# PreciseGNSS.net
KiCad netlist of a schematic drawn in Altium Designer
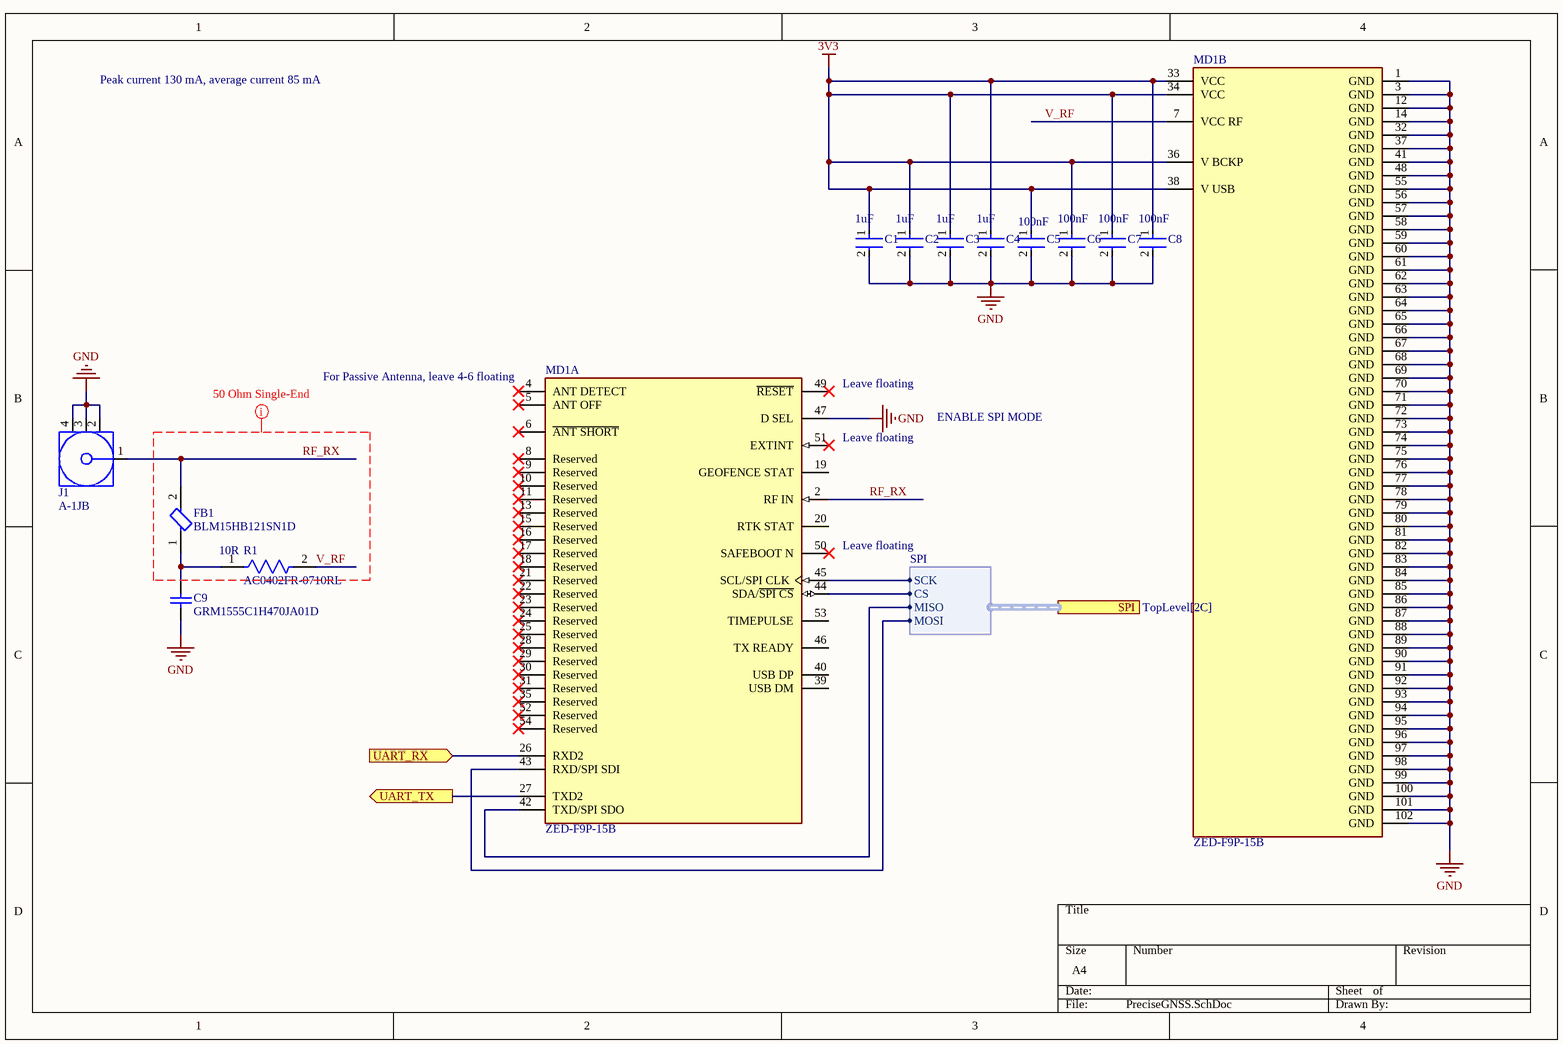
[diagram p0: PreciseGNSS.SchDoc]

(export (version "E")
  (design (tool "Eeschema 10.0.6"))
  (components
    (comp (ref "C1")
      (value "CL05A105KP5NNNC")
      (footprint "FP-CL511-IPC_C")
      (description "Cap Ceramic 1uF 10V X5R ±10% SMD 0402 +85°C Paper T/R")
      (fields (field (name "CAPACITANCE") "1uF") (field (name "TOLERANCE") "10%"))
      (libsource (lib "Altium Content Vault") (part "b4654b650e69147ec39a6b967a45e02"))
    )
    (comp (ref "C2")
      (value "CL05A105KP5NNNC")
      (footprint "FP-CL511-IPC_C")
      (description "Cap Ceramic 1uF 10V X5R ±10% SMD 0402 +85°C Paper T/R")
      (fields (field (name "CAPACITANCE") "1uF") (field (name "TOLERANCE") "10%"))
      (libsource (lib "Altium Content Vault") (part "b4654b650e69147ec39a6b967a45e02"))
    )
    (comp (ref "C3")
      (value "CL05A105KP5NNNC")
      (footprint "FP-CL511-IPC_C")
      (description "Cap Ceramic 1uF 10V X5R ±10% SMD 0402 +85°C Paper T/R")
      (fields (field (name "CAPACITANCE") "1uF") (field (name "TOLERANCE") "10%"))
      (libsource (lib "Altium Content Vault") (part "b4654b650e69147ec39a6b967a45e02"))
    )
    (comp (ref "C4")
      (value "CL05A105KP5NNNC")
      (footprint "FP-CL511-IPC_C")
      (description "Cap Ceramic 1uF 10V X5R ±10% SMD 0402 +85°C Paper T/R")
      (fields (field (name "CAPACITANCE") "1uF") (field (name "TOLERANCE") "10%"))
      (libsource (lib "Altium Content Vault") (part "b4654b650e69147ec39a6b967a45e02"))
    )
    (comp (ref "C5")
      (value "GRM155R71E104KE14J")
      (footprint "FP-GRM155-0_05-IPC_C")
      (description "Chip Multilayer Ceramic Capacitors for General Purpose, 0402, 0.10uF, X7R, 15%, 10%, 25V")
      (fields (field (name "CAPACITANCE") "100nF") (field (name "TOLERANCE") "10%"))
      (libsource (lib "Altium Content Vault") (part "02cd4be3c70576c341d710602a673aa"))
    )
    (comp (ref "C6")
      (value "GRM155R71E104KE14J")
      (footprint "FP-GRM155-0_05-IPC_C")
      (description "Chip Multilayer Ceramic Capacitors for General Purpose, 0402, 0.10uF, X7R, 15%, 10%, 25V")
      (fields (field (name "CAPACITANCE") "100nF") (field (name "TOLERANCE") "10%"))
      (libsource (lib "Altium Content Vault") (part "02cd4be3c70576c341d710602a673aa"))
    )
    (comp (ref "C7")
      (value "GRM155R71E104KE14J")
      (footprint "FP-GRM155-0_05-IPC_C")
      (description "Chip Multilayer Ceramic Capacitors for General Purpose, 0402, 0.10uF, X7R, 15%, 10%, 25V")
      (fields (field (name "CAPACITANCE") "100nF") (field (name "TOLERANCE") "10%"))
      (libsource (lib "Altium Content Vault") (part "02cd4be3c70576c341d710602a673aa"))
    )
    (comp (ref "C8")
      (value "GRM155R71E104KE14J")
      (footprint "FP-GRM155-0_05-IPC_C")
      (description "Chip Multilayer Ceramic Capacitors for General Purpose, 0402, 0.10uF, X7R, 15%, 10%, 25V")
      (fields (field (name "CAPACITANCE") "100nF") (field (name "TOLERANCE") "10%"))
      (libsource (lib "Altium Content Vault") (part "02cd4be3c70576c341d710602a673aa"))
    )
    (comp (ref "C9")
      (value "GRM1555C1H470JA01D")
      (footprint "CAPC1005X55X25LL05T10")
      (fields (field (name "MANUFACTURER") "Murata"))
      (libsource (lib "Altium Content Vault") (part "CAP"))
    )
    (comp (ref "FB1")
      (value "BLM15HB121SN1D")
      (footprint "FP-BLM15-0_05-IPC_B")
      (description "Chip Ferrite Bead, 0402, 120Ω @ 100MHz, 0.7Ω, 25%, 300mA")
      (fields (field (name "TOLERANCE") "25%"))
      (libsource (lib "Altium Content Vault") (part "5f30dd21d616792df468990f7003faa"))
    )
    (comp (ref "J1")
      (value "A-1JB")
      (footprint "AMPH-A-1JB_V")
      (description "AMC PCB Jack, 0 to 60 GHz, 60 V, -40 to 90 degC, 4-Pin SMD, RoHS, Tape and Reel")
      (fields (field (name "TOLERANCE") "10%"))
      (libsource (lib "Altium Content Vault") (part "CN-S-3F-RF4"))
    )
    (comp (ref "MD1")
      (value "ZED-F9P-15B")
      (footprint "FP-ZED-F9P-15B-MFG")
      (description "ZED-F9P-15B GNSS / GPS Modules u-blox F9 dual band L1/L5 GNSS module high precision Professi")
      (libsource (lib "Altium Content Vault") (part "967c5f9512e66fc8cb632c41bffe964"))
    )
    (comp (ref "R1")
      (value "AC0402FR-0710RL")
      (footprint "FP-AC0402-IPC_B")
      (description "RES 10Ω ±1% 0.063W 0402")
      (fields (field (name "TOLERANCE") "1%") (field (name "RESISTANCE") "10R"))
      (libsource (lib "Altium Content Vault") (part "1029c3af85768c4190bb7ad29bc67b5"))
    )
  )
  (nets
    (net (code "2") (name "/CS") (class "Default")
      (node (ref "MD1") (pin "44") (pinfunction "SDA/~{SPI_CS}_44") (pintype "bidirectional"))
    )
    (net (code "3") (name "/MISO") (class "Default")
      (node (ref "MD1") (pin "42") (pinfunction "TXD/SPI_SDO_42") (pintype "passive"))
    )
    (net (code "4") (name "/MOSI") (class "Default")
      (node (ref "MD1") (pin "43") (pinfunction "RXD/SPI_SDI_43") (pintype "passive"))
    )
    (net (code "5") (name "/RF_RX") (class "Default")
      (node (ref "FB1") (pin "2") (pinfunction "2_2") (pintype "passive"))
      (node (ref "J1") (pin "1") (pinfunction "1_1") (pintype "passive"))
      (node (ref "MD1") (pin "2") (pinfunction "RF_IN_2") (pintype "input"))
    )
    (net (code "6") (name "/SCK") (class "Default")
      (node (ref "MD1") (pin "45") (pinfunction "SCL/SPI_CLK_45") (pintype "input"))
    )
    (net (code "7") (name "/UART_RX") (class "Default")
      (node (ref "MD1") (pin "26") (pinfunction "RXD2_26") (pintype "passive"))
    )
    (net (code "8") (name "/UART_TX") (class "Default")
      (node (ref "MD1") (pin "27") (pinfunction "TXD2_27") (pintype "passive"))
    )
    (net (code "9") (name "/V_RF") (class "Default")
      (node (ref "MD1") (pin "7") (pinfunction "VCC_RF_7") (pintype "passive"))
      (node (ref "R1") (pin "2") (pinfunction "2_2") (pintype "passive"))
    )
    (net (code "11") (name "3V3") (class "Default")
      (node (ref "C1") (pin "1") (pinfunction "1_1") (pintype "passive"))
      (node (ref "C2") (pin "1") (pinfunction "1_1") (pintype "passive"))
      (node (ref "C3") (pin "1") (pinfunction "1_1") (pintype "passive"))
      (node (ref "C4") (pin "1") (pinfunction "1_1") (pintype "passive"))
      (node (ref "C5") (pin "1") (pinfunction "1_1") (pintype "passive"))
      (node (ref "C6") (pin "1") (pinfunction "1_1") (pintype "passive"))
      (node (ref "C7") (pin "1") (pinfunction "1_1") (pintype "passive"))
      (node (ref "C8") (pin "1") (pinfunction "1_1") (pintype "passive"))
      (node (ref "MD1") (pin "33") (pinfunction "VCC_33") (pintype "power_in"))
      (node (ref "MD1") (pin "34") (pinfunction "VCC_34") (pintype "power_in"))
      (node (ref "MD1") (pin "36") (pinfunction "V_BCKP_36") (pintype "passive"))
      (node (ref "MD1") (pin "38") (pinfunction "V_USB_38") (pintype "power_in"))
    )
    (net (code "12") (name "GND") (class "Default")
      (node (ref "C1") (pin "2") (pinfunction "2_2") (pintype "passive"))
      (node (ref "C2") (pin "2") (pinfunction "2_2") (pintype "passive"))
      (node (ref "C3") (pin "2") (pinfunction "2_2") (pintype "passive"))
      (node (ref "C4") (pin "2") (pinfunction "2_2") (pintype "passive"))
      (node (ref "C5") (pin "2") (pinfunction "2_2") (pintype "passive"))
      (node (ref "C6") (pin "2") (pinfunction "2_2") (pintype "passive"))
      (node (ref "C7") (pin "2") (pinfunction "2_2") (pintype "passive"))
      (node (ref "C8") (pin "2") (pinfunction "2_2") (pintype "passive"))
      (node (ref "C9") (pin "1") (pinfunction "1_1") (pintype "passive"))
      (node (ref "J1") (pin "2") (pinfunction "2_2") (pintype "passive"))
      (node (ref "J1") (pin "3") (pinfunction "3_3") (pintype "passive"))
      (node (ref "J1") (pin "4") (pinfunction "4_4") (pintype "passive"))
      (node (ref "MD1") (pin "1") (pinfunction "GND_1") (pintype "power_in"))
      (node (ref "MD1") (pin "100") (pinfunction "GND_100") (pintype "power_in"))
      (node (ref "MD1") (pin "101") (pinfunction "GND_101") (pintype "power_in"))
      (node (ref "MD1") (pin "102") (pinfunction "GND_102") (pintype "power_in"))
      (node (ref "MD1") (pin "12") (pinfunction "GND_12") (pintype "power_in"))
      (node (ref "MD1") (pin "14") (pinfunction "GND_14") (pintype "power_in"))
      (node (ref "MD1") (pin "3") (pinfunction "GND_3") (pintype "power_in"))
      (node (ref "MD1") (pin "32") (pinfunction "GND_32") (pintype "power_in"))
      (node (ref "MD1") (pin "37") (pinfunction "GND_37") (pintype "power_in"))
      (node (ref "MD1") (pin "41") (pinfunction "GND_41") (pintype "power_in"))
      (node (ref "MD1") (pin "47") (pinfunction "D_SEL_47") (pintype "passive"))
      (node (ref "MD1") (pin "48") (pinfunction "GND_48") (pintype "power_in"))
      (node (ref "MD1") (pin "55") (pinfunction "GND_55") (pintype "power_in"))
      (node (ref "MD1") (pin "56") (pinfunction "GND_56") (pintype "power_in"))
      (node (ref "MD1") (pin "57") (pinfunction "GND_57") (pintype "power_in"))
      (node (ref "MD1") (pin "58") (pinfunction "GND_58") (pintype "power_in"))
      (node (ref "MD1") (pin "59") (pinfunction "GND_59") (pintype "power_in"))
      (node (ref "MD1") (pin "60") (pinfunction "GND_60") (pintype "power_in"))
      (node (ref "MD1") (pin "61") (pinfunction "GND_61") (pintype "power_in"))
      (node (ref "MD1") (pin "62") (pinfunction "GND_62") (pintype "power_in"))
      (node (ref "MD1") (pin "63") (pinfunction "GND_63") (pintype "power_in"))
      (node (ref "MD1") (pin "64") (pinfunction "GND_64") (pintype "power_in"))
      (node (ref "MD1") (pin "65") (pinfunction "GND_65") (pintype "power_in"))
      (node (ref "MD1") (pin "66") (pinfunction "GND_66") (pintype "power_in"))
      (node (ref "MD1") (pin "67") (pinfunction "GND_67") (pintype "power_in"))
      (node (ref "MD1") (pin "68") (pinfunction "GND_68") (pintype "power_in"))
      (node (ref "MD1") (pin "69") (pinfunction "GND_69") (pintype "power_in"))
      (node (ref "MD1") (pin "70") (pinfunction "GND_70") (pintype "power_in"))
      (node (ref "MD1") (pin "71") (pinfunction "GND_71") (pintype "power_in"))
      (node (ref "MD1") (pin "72") (pinfunction "GND_72") (pintype "power_in"))
      (node (ref "MD1") (pin "73") (pinfunction "GND_73") (pintype "power_in"))
      (node (ref "MD1") (pin "74") (pinfunction "GND_74") (pintype "power_in"))
      (node (ref "MD1") (pin "75") (pinfunction "GND_75") (pintype "power_in"))
      (node (ref "MD1") (pin "76") (pinfunction "GND_76") (pintype "power_in"))
      (node (ref "MD1") (pin "77") (pinfunction "GND_77") (pintype "power_in"))
      (node (ref "MD1") (pin "78") (pinfunction "GND_78") (pintype "power_in"))
      (node (ref "MD1") (pin "79") (pinfunction "GND_79") (pintype "power_in"))
      (node (ref "MD1") (pin "80") (pinfunction "GND_80") (pintype "power_in"))
      (node (ref "MD1") (pin "81") (pinfunction "GND_81") (pintype "power_in"))
      (node (ref "MD1") (pin "82") (pinfunction "GND_82") (pintype "power_in"))
      (node (ref "MD1") (pin "83") (pinfunction "GND_83") (pintype "power_in"))
      (node (ref "MD1") (pin "84") (pinfunction "GND_84") (pintype "power_in"))
      (node (ref "MD1") (pin "85") (pinfunction "GND_85") (pintype "power_in"))
      (node (ref "MD1") (pin "86") (pinfunction "GND_86") (pintype "power_in"))
      (node (ref "MD1") (pin "87") (pinfunction "GND_87") (pintype "power_in"))
      (node (ref "MD1") (pin "88") (pinfunction "GND_88") (pintype "power_in"))
      (node (ref "MD1") (pin "89") (pinfunction "GND_89") (pintype "power_in"))
      (node (ref "MD1") (pin "90") (pinfunction "GND_90") (pintype "power_in"))
      (node (ref "MD1") (pin "91") (pinfunction "GND_91") (pintype "power_in"))
      (node (ref "MD1") (pin "92") (pinfunction "GND_92") (pintype "power_in"))
      (node (ref "MD1") (pin "93") (pinfunction "GND_93") (pintype "power_in"))
      (node (ref "MD1") (pin "94") (pinfunction "GND_94") (pintype "power_in"))
      (node (ref "MD1") (pin "95") (pinfunction "GND_95") (pintype "power_in"))
      (node (ref "MD1") (pin "96") (pinfunction "GND_96") (pintype "power_in"))
      (node (ref "MD1") (pin "97") (pinfunction "GND_97") (pintype "power_in"))
      (node (ref "MD1") (pin "98") (pinfunction "GND_98") (pintype "power_in"))
      (node (ref "MD1") (pin "99") (pinfunction "GND_99") (pintype "power_in"))
    )
    (net (code "13") (name "Net-(C9-Pad2)") (class "Default")
      (node (ref "C9") (pin "2") (pinfunction "2_2") (pintype "passive"))
      (node (ref "FB1") (pin "1") (pinfunction "1_1") (pintype "passive"))
      (node (ref "R1") (pin "1") (pinfunction "1_1") (pintype "passive"))
    )
    (net (code "14") (name "unconnected-(MD1A-ANT_DETECT-Pad4)") (class "Default")
      (node (ref "MD1") (pin "4") (pinfunction "ANT_DETECT_4") (pintype "passive+no_connect"))
    )
    (net (code "15") (name "unconnected-(MD1A-ANT_OFF-Pad5)") (class "Default")
      (node (ref "MD1") (pin "5") (pinfunction "ANT_OFF_5") (pintype "passive+no_connect"))
    )
    (net (code "16") (name "unconnected-(MD1A-EXTINT-Pad51)") (class "Default")
      (node (ref "MD1") (pin "51") (pinfunction "EXTINT_51") (pintype "input+no_connect"))
    )
    (net (code "17") (name "unconnected-(MD1A-GEOFENCE_STAT-Pad19)") (class "Default")
      (node (ref "MD1") (pin "19") (pinfunction "GEOFENCE_STAT_19") (pintype "passive"))
    )
    (net (code "18") (name "unconnected-(MD1A-RTK_STAT-Pad20)") (class "Default")
      (node (ref "MD1") (pin "20") (pinfunction "RTK_STAT_20") (pintype "passive"))
    )
    (net (code "19") (name "unconnected-(MD1A-Reserved-Pad8)") (class "Default")
      (node (ref "MD1") (pin "8") (pinfunction "Reserved_8") (pintype "passive+no_connect"))
    )
    (net (code "20") (name "unconnected-(MD1A-Reserved-Pad9)") (class "Default")
      (node (ref "MD1") (pin "9") (pinfunction "Reserved_9") (pintype "passive+no_connect"))
    )
    (net (code "21") (name "unconnected-(MD1A-Reserved-Pad10)") (class "Default")
      (node (ref "MD1") (pin "10") (pinfunction "Reserved_10") (pintype "passive+no_connect"))
    )
    (net (code "22") (name "unconnected-(MD1A-Reserved-Pad11)") (class "Default")
      (node (ref "MD1") (pin "11") (pinfunction "Reserved_11") (pintype "passive+no_connect"))
    )
    (net (code "23") (name "unconnected-(MD1A-Reserved-Pad13)") (class "Default")
      (node (ref "MD1") (pin "13") (pinfunction "Reserved_13") (pintype "passive+no_connect"))
    )
    (net (code "24") (name "unconnected-(MD1A-Reserved-Pad15)") (class "Default")
      (node (ref "MD1") (pin "15") (pinfunction "Reserved_15") (pintype "passive+no_connect"))
    )
    (net (code "25") (name "unconnected-(MD1A-Reserved-Pad16)") (class "Default")
      (node (ref "MD1") (pin "16") (pinfunction "Reserved_16") (pintype "passive+no_connect"))
    )
    (net (code "26") (name "unconnected-(MD1A-Reserved-Pad17)") (class "Default")
      (node (ref "MD1") (pin "17") (pinfunction "Reserved_17") (pintype "passive+no_connect"))
    )
    (net (code "27") (name "unconnected-(MD1A-Reserved-Pad18)") (class "Default")
      (node (ref "MD1") (pin "18") (pinfunction "Reserved_18") (pintype "passive+no_connect"))
    )
    (net (code "28") (name "unconnected-(MD1A-Reserved-Pad21)") (class "Default")
      (node (ref "MD1") (pin "21") (pinfunction "Reserved_21") (pintype "passive+no_connect"))
    )
    (net (code "29") (name "unconnected-(MD1A-Reserved-Pad22)") (class "Default")
      (node (ref "MD1") (pin "22") (pinfunction "Reserved_22") (pintype "passive+no_connect"))
    )
    (net (code "30") (name "unconnected-(MD1A-Reserved-Pad23)") (class "Default")
      (node (ref "MD1") (pin "23") (pinfunction "Reserved_23") (pintype "passive+no_connect"))
    )
    (net (code "31") (name "unconnected-(MD1A-Reserved-Pad24)") (class "Default")
      (node (ref "MD1") (pin "24") (pinfunction "Reserved_24") (pintype "passive+no_connect"))
    )
    (net (code "32") (name "unconnected-(MD1A-Reserved-Pad25)") (class "Default")
      (node (ref "MD1") (pin "25") (pinfunction "Reserved_25") (pintype "passive+no_connect"))
    )
    (net (code "33") (name "unconnected-(MD1A-Reserved-Pad28)") (class "Default")
      (node (ref "MD1") (pin "28") (pinfunction "Reserved_28") (pintype "passive+no_connect"))
    )
    (net (code "34") (name "unconnected-(MD1A-Reserved-Pad29)") (class "Default")
      (node (ref "MD1") (pin "29") (pinfunction "Reserved_29") (pintype "passive+no_connect"))
    )
    (net (code "35") (name "unconnected-(MD1A-Reserved-Pad30)") (class "Default")
      (node (ref "MD1") (pin "30") (pinfunction "Reserved_30") (pintype "passive+no_connect"))
    )
    (net (code "36") (name "unconnected-(MD1A-Reserved-Pad31)") (class "Default")
      (node (ref "MD1") (pin "31") (pinfunction "Reserved_31") (pintype "passive+no_connect"))
    )
    (net (code "37") (name "unconnected-(MD1A-Reserved-Pad35)") (class "Default")
      (node (ref "MD1") (pin "35") (pinfunction "Reserved_35") (pintype "passive+no_connect"))
    )
    (net (code "38") (name "unconnected-(MD1A-Reserved-Pad52)") (class "Default")
      (node (ref "MD1") (pin "52") (pinfunction "Reserved_52") (pintype "passive+no_connect"))
    )
    (net (code "39") (name "unconnected-(MD1A-Reserved-Pad54)") (class "Default")
      (node (ref "MD1") (pin "54") (pinfunction "Reserved_54") (pintype "passive+no_connect"))
    )
    (net (code "40") (name "unconnected-(MD1A-SAFEBOOT_N-Pad50)") (class "Default")
      (node (ref "MD1") (pin "50") (pinfunction "SAFEBOOT_N_50") (pintype "passive+no_connect"))
    )
    (net (code "41") (name "unconnected-(MD1A-TIMEPULSE-Pad53)") (class "Default")
      (node (ref "MD1") (pin "53") (pinfunction "TIMEPULSE_53") (pintype "passive"))
    )
    (net (code "42") (name "unconnected-(MD1A-TX_READY-Pad46)") (class "Default")
      (node (ref "MD1") (pin "46") (pinfunction "TX_READY_46") (pintype "passive"))
    )
    (net (code "43") (name "unconnected-(MD1A-USB_DM-Pad39)") (class "Default")
      (node (ref "MD1") (pin "39") (pinfunction "USB_DM_39") (pintype "passive"))
    )
    (net (code "44") (name "unconnected-(MD1A-USB_DP-Pad40)") (class "Default")
      (node (ref "MD1") (pin "40") (pinfunction "USB_DP_40") (pintype "passive"))
    )
    (net (code "45") (name "unconnected-(MD1A-~{ANT_SHORT}-Pad6)") (class "Default")
      (node (ref "MD1") (pin "6") (pinfunction "~{ANT_SHORT}_6") (pintype "passive+no_connect"))
    )
    (net (code "46") (name "unconnected-(MD1A-~{RESET}-Pad49)") (class "Default")
      (node (ref "MD1") (pin "49") (pinfunction "~{RESET}_49") (pintype "passive+no_connect"))
    )
  )
)
